# arm_arduinoboard.net
KiCad netlist of a schematic drawn in EAGLE
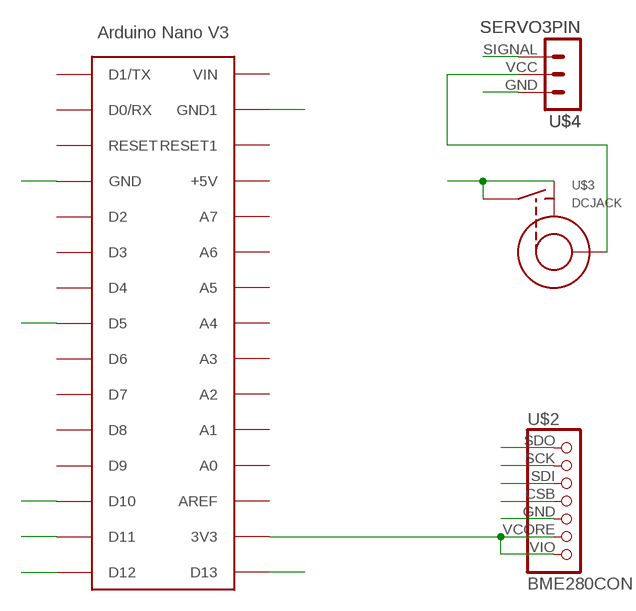
[diagram p0: schematic, sheet 1]

(export (version "E")
  (design (tool "Eeschema 10.0.6"))
  (components
    (comp (ref "U$1")
      (value "ARDUINO_NANO")
      (footprint "eagle-import:ARDUINO_NANO")
      (libsource (lib "eagle-import") (part "ARDUINO_NANO"))
    )
    (comp (ref "U$2")
      (value "BME280CON")
      (footprint "eagle-import:BME280CON")
      (libsource (lib "eagle-import") (part "BME280CON"))
    )
    (comp (ref "U$3")
      (value "DCJACK")
      (footprint "eagle-import:DCJACK")
      (libsource (lib "eagle-import") (part "DCJACK"))
    )
    (comp (ref "U$4")
      (value "SERVO3PIN")
      (footprint "eagle-import:SERVO3PIN")
      (libsource (lib "eagle-import") (part "SERVO3PIN"))
    )
  )
  (nets
    (net (code "1") (name "/CSB") (class "Default")
      (node (ref "U$1") (pin "D10") (pinfunction "D10_D10") (pintype "bidirectional"))
      (node (ref "U$2") (pin "CSB") (pinfunction "CSB_CSB") (pintype "passive"))
    )
    (net (code "2") (name "/GND") (class "Default")
      (node (ref "U$1") (pin "GND") (pinfunction "GND_GND") (pintype "bidirectional"))
      (node (ref "U$1") (pin "GND1") (pinfunction "GND1_GND1") (pintype "bidirectional"))
      (node (ref "U$2") (pin "GND") (pinfunction "GND_GND") (pintype "passive"))
      (node (ref "U$3") (pin "P$2") (pinfunction "TIP_P$2") (pintype "passive"))
      (node (ref "U$3") (pin "P$3") (pinfunction "SHUNT_P$3") (pintype "passive"))
      (node (ref "U$4") (pin "GND") (pinfunction "GND_GND") (pintype "passive"))
    )
    (net (code "3") (name "/SCK") (class "Default")
      (node (ref "U$1") (pin "D13") (pinfunction "D13_D13") (pintype "bidirectional"))
      (node (ref "U$2") (pin "SCK") (pinfunction "SCK_SCK") (pintype "passive"))
    )
    (net (code "4") (name "/SDI") (class "Default")
      (node (ref "U$1") (pin "D11") (pinfunction "D11_D11") (pintype "bidirectional"))
      (node (ref "U$2") (pin "SDI") (pinfunction "SDI_SDI") (pintype "passive"))
    )
    (net (code "5") (name "/SDO") (class "Default")
      (node (ref "U$1") (pin "D12") (pinfunction "D12_D12") (pintype "bidirectional"))
      (node (ref "U$2") (pin "SDO") (pinfunction "SDO_SDO") (pintype "passive"))
    )
    (net (code "6") (name "/SIGNAL") (class "Default")
      (node (ref "U$1") (pin "D5") (pinfunction "D5_D5") (pintype "bidirectional"))
      (node (ref "U$4") (pin "SIGNAL") (pinfunction "SIGNAL_SIGNAL") (pintype "passive"))
    )
    (net (code "7") (name "Net-(U$1-Pad3V3)") (class "Default")
      (node (ref "U$1") (pin "3V3") (pinfunction "3V3_3V3") (pintype "bidirectional"))
      (node (ref "U$2") (pin "VCORE") (pinfunction "VCORE_VCORE") (pintype "passive"))
      (node (ref "U$2") (pin "VIO") (pinfunction "VIO_VIO") (pintype "passive"))
    )
    (net (code "8") (name "Net-(U$3-CENTER)") (class "Default")
      (node (ref "U$3") (pin "P$1") (pinfunction "CENTER_P$1") (pintype "passive"))
      (node (ref "U$4") (pin "VCC") (pinfunction "VCC_VCC") (pintype "passive"))
    )
    (net (code "9") (name "unconnected-(U$1-A0-PadA7)") (class "Default")
      (node (ref "U$1") (pin "A7") (pinfunction "A0_A7") (pintype "bidirectional"))
    )
    (net (code "10") (name "unconnected-(U$1-A1-PadA6)") (class "Default")
      (node (ref "U$1") (pin "A6") (pinfunction "A1_A6") (pintype "bidirectional"))
    )
    (net (code "11") (name "unconnected-(U$1-A2-PadA5)") (class "Default")
      (node (ref "U$1") (pin "A5") (pinfunction "A2_A5") (pintype "bidirectional"))
    )
    (net (code "12") (name "unconnected-(U$1-A3-PadA4)") (class "Default")
      (node (ref "U$1") (pin "A4") (pinfunction "A3_A4") (pintype "bidirectional"))
    )
    (net (code "13") (name "unconnected-(U$1-A4-PadA3)") (class "Default")
      (node (ref "U$1") (pin "A3") (pinfunction "A4_A3") (pintype "bidirectional"))
    )
    (net (code "14") (name "unconnected-(U$1-A5-PadA2)") (class "Default")
      (node (ref "U$1") (pin "A2") (pinfunction "A5_A2") (pintype "bidirectional"))
    )
    (net (code "15") (name "unconnected-(U$1-A6-PadA1)") (class "Default")
      (node (ref "U$1") (pin "A1") (pinfunction "A6_A1") (pintype "bidirectional"))
    )
    (net (code "16") (name "unconnected-(U$1-A7-PadA0)") (class "Default")
      (node (ref "U$1") (pin "A0") (pinfunction "A7_A0") (pintype "bidirectional"))
    )
    (net (code "17") (name "unconnected-(U$1-Pad+5V)") (class "Default")
      (node (ref "U$1") (pin "+5V") (pinfunction "+5V_+5V") (pintype "bidirectional"))
    )
    (net (code "18") (name "unconnected-(U$1-PadAREF)") (class "Default")
      (node (ref "U$1") (pin "AREF") (pinfunction "AREF_AREF") (pintype "bidirectional"))
    )
    (net (code "19") (name "unconnected-(U$1-PadD0{slash}RX)") (class "Default")
      (node (ref "U$1") (pin "D0/RX") (pinfunction "D0/RX_D0/RX") (pintype "bidirectional"))
    )
    (net (code "20") (name "unconnected-(U$1-PadD1{slash}TX)") (class "Default")
      (node (ref "U$1") (pin "D1/TX") (pinfunction "D1/TX_D1/TX") (pintype "bidirectional"))
    )
    (net (code "21") (name "unconnected-(U$1-PadD2)") (class "Default")
      (node (ref "U$1") (pin "D2") (pinfunction "D2_D2") (pintype "bidirectional"))
    )
    (net (code "22") (name "unconnected-(U$1-PadD3)") (class "Default")
      (node (ref "U$1") (pin "D3") (pinfunction "D3_D3") (pintype "bidirectional"))
    )
    (net (code "23") (name "unconnected-(U$1-PadD4)") (class "Default")
      (node (ref "U$1") (pin "D4") (pinfunction "D4_D4") (pintype "bidirectional"))
    )
    (net (code "24") (name "unconnected-(U$1-PadD6)") (class "Default")
      (node (ref "U$1") (pin "D6") (pinfunction "D6_D6") (pintype "bidirectional"))
    )
    (net (code "25") (name "unconnected-(U$1-PadD7)") (class "Default")
      (node (ref "U$1") (pin "D7") (pinfunction "D7_D7") (pintype "bidirectional"))
    )
    (net (code "26") (name "unconnected-(U$1-PadD8)") (class "Default")
      (node (ref "U$1") (pin "D8") (pinfunction "D8_D8") (pintype "bidirectional"))
    )
    (net (code "27") (name "unconnected-(U$1-PadD9)") (class "Default")
      (node (ref "U$1") (pin "D9") (pinfunction "D9_D9") (pintype "bidirectional"))
    )
    (net (code "28") (name "unconnected-(U$1-PadRESET)") (class "Default")
      (node (ref "U$1") (pin "RESET") (pinfunction "RESET_RESET") (pintype "bidirectional"))
    )
    (net (code "29") (name "unconnected-(U$1-PadRESET1)") (class "Default")
      (node (ref "U$1") (pin "RESET1") (pinfunction "RESET1_RESET1") (pintype "bidirectional"))
    )
    (net (code "30") (name "unconnected-(U$1-PadVIN)") (class "Default")
      (node (ref "U$1") (pin "VIN") (pinfunction "VIN_VIN") (pintype "bidirectional"))
    )
  )
)
